# 08_LMS7002M_2_Power.net
KiCad netlist of a schematic drawn in Altium Designer
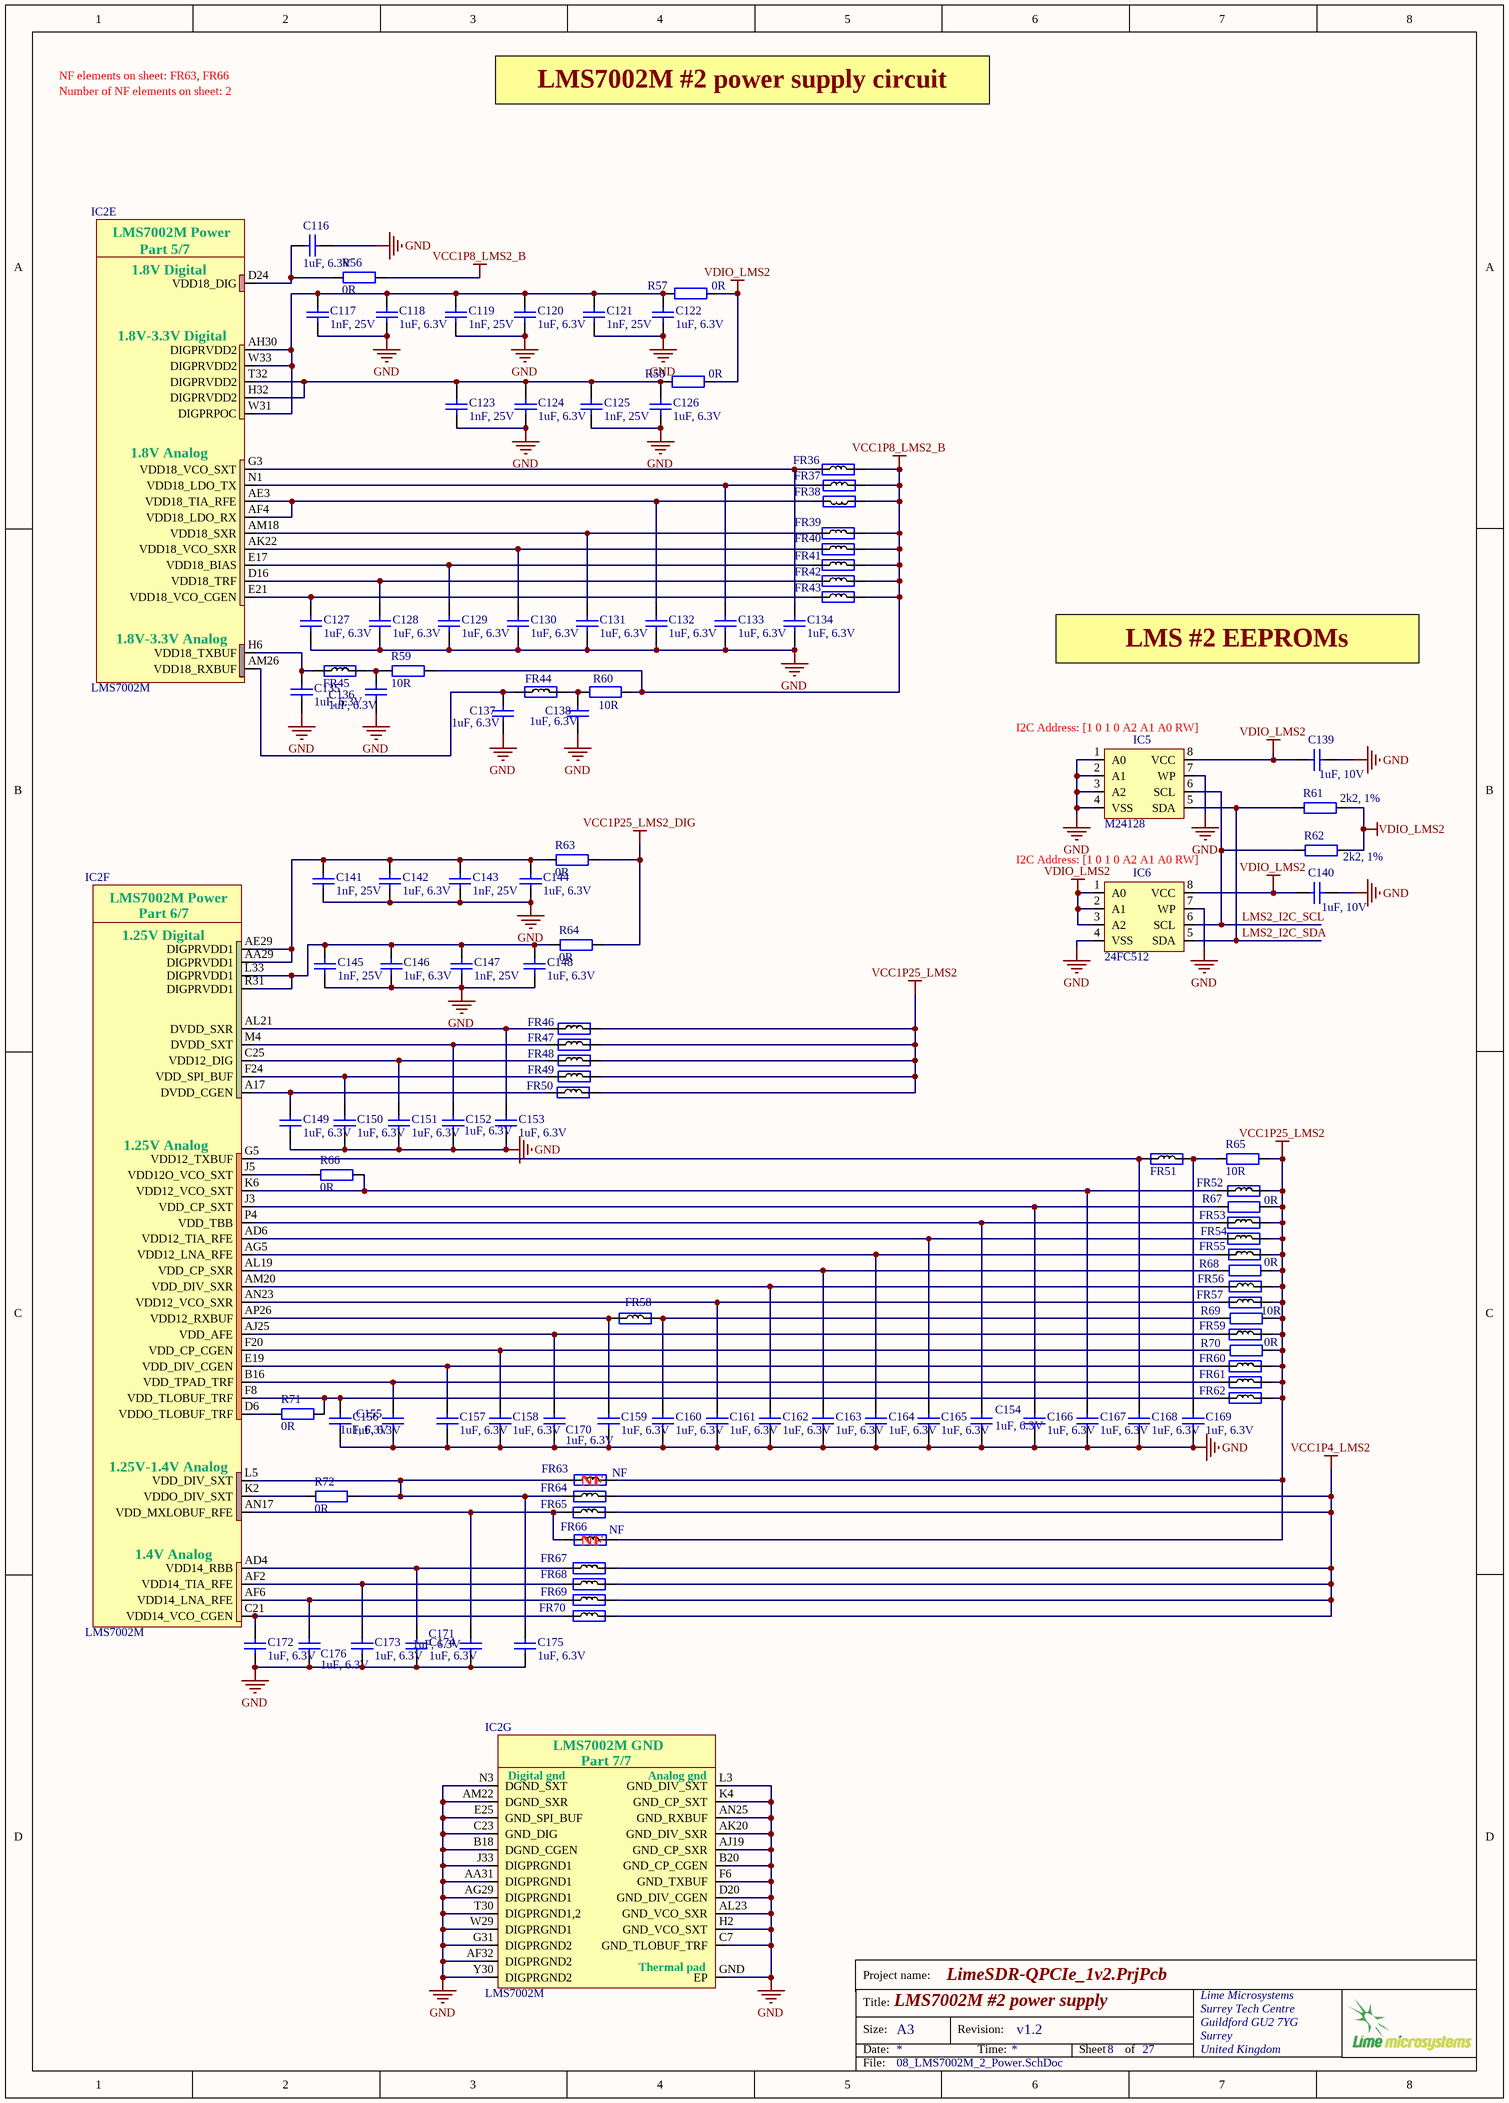
[diagram p0: 08_LMS7002M_2_Power.SchDoc]

(export (version "E")
  (design (tool "Eeschema 10.0.6"))
  (components
    (comp (ref "C116")
      (value "1uF, 6.3V")
      (footprint "CAP0201")
      (fields (field (name "TOLERANCE") "±20%") (field (name "MANUFACTURER") "TDK Corporation"))
      (libsource (lib "LimeMicroAltiumLib_schLib") (part "Cap_0402"))
    )
    (comp (ref "C117")
      (value "1nF, 25V")
      (footprint "CAP0201")
      (fields (field (name "TOLERANCE") "±10%") (field (name "MANUFACTURER") "TDK Corporation"))
      (libsource (lib "LimeMicroAltiumLib_schLib") (part "Cap_0402"))
    )
    (comp (ref "C118")
      (value "1uF, 6.3V")
      (footprint "CAP0201")
      (fields (field (name "TOLERANCE") "±20%") (field (name "MANUFACTURER") "TDK Corporation"))
      (libsource (lib "LimeMicroAltiumLib_schLib") (part "Cap_0402"))
    )
    (comp (ref "C119")
      (value "1nF, 25V")
      (footprint "CAP0201")
      (fields (field (name "TOLERANCE") "±10%") (field (name "MANUFACTURER") "TDK Corporation"))
      (libsource (lib "LimeMicroAltiumLib_schLib") (part "Cap_0402"))
    )
    (comp (ref "C120")
      (value "1uF, 6.3V")
      (footprint "CAP0201")
      (fields (field (name "TOLERANCE") "±20%") (field (name "MANUFACTURER") "TDK Corporation"))
      (libsource (lib "LimeMicroAltiumLib_schLib") (part "Cap_0402"))
    )
    (comp (ref "C121")
      (value "1nF, 25V")
      (footprint "CAP0201")
      (fields (field (name "TOLERANCE") "±10%") (field (name "MANUFACTURER") "TDK Corporation"))
      (libsource (lib "LimeMicroAltiumLib_schLib") (part "Cap_0402"))
    )
    (comp (ref "C122")
      (value "1uF, 6.3V")
      (footprint "CAP0201")
      (fields (field (name "TOLERANCE") "±20%") (field (name "MANUFACTURER") "TDK Corporation"))
      (libsource (lib "LimeMicroAltiumLib_schLib") (part "Cap_0402"))
    )
    (comp (ref "C123")
      (value "1nF, 25V")
      (footprint "CAP0201")
      (fields (field (name "TOLERANCE") "±10%") (field (name "MANUFACTURER") "TDK Corporation"))
      (libsource (lib "LimeMicroAltiumLib_schLib") (part "Cap_0402"))
    )
    (comp (ref "C124")
      (value "1uF, 6.3V")
      (footprint "CAP0201")
      (fields (field (name "TOLERANCE") "±20%") (field (name "MANUFACTURER") "TDK Corporation"))
      (libsource (lib "LimeMicroAltiumLib_schLib") (part "Cap_0402"))
    )
    (comp (ref "C125")
      (value "1nF, 25V")
      (footprint "CAP0201")
      (fields (field (name "TOLERANCE") "±10%") (field (name "MANUFACTURER") "TDK Corporation"))
      (libsource (lib "LimeMicroAltiumLib_schLib") (part "Cap_0402"))
    )
    (comp (ref "C126")
      (value "1uF, 6.3V")
      (footprint "CAP0201")
      (fields (field (name "TOLERANCE") "±20%") (field (name "MANUFACTURER") "TDK Corporation"))
      (libsource (lib "LimeMicroAltiumLib_schLib") (part "Cap_0402"))
    )
    (comp (ref "C127")
      (value "1uF, 6.3V")
      (footprint "CAP0201")
      (fields (field (name "TOLERANCE") "±20%") (field (name "MANUFACTURER") "TDK Corporation"))
      (libsource (lib "LimeMicroAltiumLib_schLib") (part "Cap_0402"))
    )
    (comp (ref "C128")
      (value "1uF, 6.3V")
      (footprint "CAP0201")
      (fields (field (name "TOLERANCE") "±20%") (field (name "MANUFACTURER") "TDK Corporation"))
      (libsource (lib "LimeMicroAltiumLib_schLib") (part "Cap_0402"))
    )
    (comp (ref "C129")
      (value "1uF, 6.3V")
      (footprint "CAP0201")
      (fields (field (name "TOLERANCE") "±20%") (field (name "MANUFACTURER") "TDK Corporation"))
      (libsource (lib "LimeMicroAltiumLib_schLib") (part "Cap_0402"))
    )
    (comp (ref "C130")
      (value "1uF, 6.3V")
      (footprint "CAP0201")
      (fields (field (name "TOLERANCE") "±20%") (field (name "MANUFACTURER") "TDK Corporation"))
      (libsource (lib "LimeMicroAltiumLib_schLib") (part "Cap_0402"))
    )
    (comp (ref "C131")
      (value "1uF, 6.3V")
      (footprint "CAP0201")
      (fields (field (name "TOLERANCE") "±20%") (field (name "MANUFACTURER") "TDK Corporation"))
      (libsource (lib "LimeMicroAltiumLib_schLib") (part "Cap_0402"))
    )
    (comp (ref "C132")
      (value "1uF, 6.3V")
      (footprint "CAP0201")
      (fields (field (name "TOLERANCE") "±20%") (field (name "MANUFACTURER") "TDK Corporation"))
      (libsource (lib "LimeMicroAltiumLib_schLib") (part "Cap_0402"))
    )
    (comp (ref "C133")
      (value "1uF, 6.3V")
      (footprint "CAP0201")
      (fields (field (name "TOLERANCE") "±20%") (field (name "MANUFACTURER") "TDK Corporation"))
      (libsource (lib "LimeMicroAltiumLib_schLib") (part "Cap_0402"))
    )
    (comp (ref "C134")
      (value "1uF, 6.3V")
      (footprint "CAP0201")
      (fields (field (name "TOLERANCE") "±20%") (field (name "MANUFACTURER") "TDK Corporation"))
      (libsource (lib "LimeMicroAltiumLib_schLib") (part "Cap_0402"))
    )
    (comp (ref "C135")
      (value "1uF, 6.3V")
      (footprint "CAP0201")
      (fields (field (name "TOLERANCE") "±20%") (field (name "MANUFACTURER") "TDK Corporation"))
      (libsource (lib "LimeMicroAltiumLib_schLib") (part "Cap_0402"))
    )
    (comp (ref "C136")
      (value "1uF, 6.3V")
      (footprint "CAP0201")
      (fields (field (name "TOLERANCE") "±20%") (field (name "MANUFACTURER") "TDK Corporation"))
      (libsource (lib "LimeMicroAltiumLib_schLib") (part "Cap_0402"))
    )
    (comp (ref "C137")
      (value "1uF, 6.3V")
      (footprint "CAP0201")
      (fields (field (name "TOLERANCE") "±20%") (field (name "MANUFACTURER") "TDK Corporation"))
      (libsource (lib "LimeMicroAltiumLib_schLib") (part "Cap_0402"))
    )
    (comp (ref "C138")
      (value "1uF, 6.3V")
      (footprint "CAP0201")
      (fields (field (name "TOLERANCE") "±20%") (field (name "MANUFACTURER") "TDK Corporation"))
      (libsource (lib "LimeMicroAltiumLib_schLib") (part "Cap_0402"))
    )
    (comp (ref "C139")
      (value "1uF, 10V")
      (footprint "CAP0402")
      (fields (field (name "MANUFACTURER") "TDK"))
      (libsource (lib "LimeMicroAltiumLib_schLib") (part "Cap_0402"))
    )
    (comp (ref "C140")
      (value "1uF, 10V")
      (footprint "CAP0402")
      (fields (field (name "MANUFACTURER") "TDK"))
      (libsource (lib "LimeMicroAltiumLib_schLib") (part "Cap_0402"))
    )
    (comp (ref "C141")
      (value "1nF, 25V")
      (footprint "CAP0201")
      (fields (field (name "TOLERANCE") "±10%") (field (name "MANUFACTURER") "TDK Corporation"))
      (libsource (lib "LimeMicroAltiumLib_schLib") (part "Cap_0402"))
    )
    (comp (ref "C142")
      (value "1uF, 6.3V")
      (footprint "CAP0201")
      (fields (field (name "TOLERANCE") "±20%") (field (name "MANUFACTURER") "TDK Corporation"))
      (libsource (lib "LimeMicroAltiumLib_schLib") (part "Cap_0402"))
    )
    (comp (ref "C143")
      (value "1nF, 25V")
      (footprint "CAP0201")
      (fields (field (name "TOLERANCE") "±10%") (field (name "MANUFACTURER") "TDK Corporation"))
      (libsource (lib "LimeMicroAltiumLib_schLib") (part "Cap_0402"))
    )
    (comp (ref "C144")
      (value "1uF, 6.3V")
      (footprint "CAP0201")
      (fields (field (name "TOLERANCE") "±20%") (field (name "MANUFACTURER") "TDK Corporation"))
      (libsource (lib "LimeMicroAltiumLib_schLib") (part "Cap_0402"))
    )
    (comp (ref "C145")
      (value "1nF, 25V")
      (footprint "CAP0201")
      (fields (field (name "TOLERANCE") "±10%") (field (name "MANUFACTURER") "TDK Corporation"))
      (libsource (lib "LimeMicroAltiumLib_schLib") (part "Cap_0402"))
    )
    (comp (ref "C146")
      (value "1uF, 6.3V")
      (footprint "CAP0201")
      (fields (field (name "TOLERANCE") "±20%") (field (name "MANUFACTURER") "TDK Corporation"))
      (libsource (lib "LimeMicroAltiumLib_schLib") (part "Cap_0402"))
    )
    (comp (ref "C147")
      (value "1nF, 25V")
      (footprint "CAP0201")
      (fields (field (name "TOLERANCE") "±10%") (field (name "MANUFACTURER") "TDK Corporation"))
      (libsource (lib "LimeMicroAltiumLib_schLib") (part "Cap_0402"))
    )
    (comp (ref "C148")
      (value "1uF, 6.3V")
      (footprint "CAP0201")
      (fields (field (name "TOLERANCE") "±20%") (field (name "MANUFACTURER") "TDK Corporation"))
      (libsource (lib "LimeMicroAltiumLib_schLib") (part "Cap_0402"))
    )
    (comp (ref "C149")
      (value "1uF, 6.3V")
      (footprint "CAP0201")
      (fields (field (name "TOLERANCE") "±20%") (field (name "MANUFACTURER") "TDK Corporation"))
      (libsource (lib "LimeMicroAltiumLib_schLib") (part "Cap_0402"))
    )
    (comp (ref "C150")
      (value "1uF, 6.3V")
      (footprint "CAP0201")
      (fields (field (name "TOLERANCE") "±20%") (field (name "MANUFACTURER") "TDK Corporation"))
      (libsource (lib "LimeMicroAltiumLib_schLib") (part "Cap_0402"))
    )
    (comp (ref "C151")
      (value "1uF, 6.3V")
      (footprint "CAP0201")
      (fields (field (name "TOLERANCE") "±20%") (field (name "MANUFACTURER") "TDK Corporation"))
      (libsource (lib "LimeMicroAltiumLib_schLib") (part "Cap_0402"))
    )
    (comp (ref "C152")
      (value "1uF, 6.3V")
      (footprint "CAP0201")
      (fields (field (name "TOLERANCE") "±20%") (field (name "MANUFACTURER") "TDK Corporation"))
      (libsource (lib "LimeMicroAltiumLib_schLib") (part "Cap_0402"))
    )
    (comp (ref "C153")
      (value "1uF, 6.3V")
      (footprint "CAP0201")
      (fields (field (name "TOLERANCE") "±20%") (field (name "MANUFACTURER") "TDK Corporation"))
      (libsource (lib "LimeMicroAltiumLib_schLib") (part "Cap_0402"))
    )
    (comp (ref "C154")
      (value "1uF, 6.3V")
      (footprint "CAP0201")
      (fields (field (name "TOLERANCE") "±20%") (field (name "MANUFACTURER") "TDK Corporation"))
      (libsource (lib "LimeMicroAltiumLib_schLib") (part "Cap_0402"))
    )
    (comp (ref "C155")
      (value "1uF, 6.3V")
      (footprint "CAP0201")
      (fields (field (name "TOLERANCE") "±20%") (field (name "MANUFACTURER") "TDK Corporation"))
      (libsource (lib "LimeMicroAltiumLib_schLib") (part "Cap_0402"))
    )
    (comp (ref "C156")
      (value "1uF, 6.3V")
      (footprint "CAP0201")
      (fields (field (name "TOLERANCE") "±20%") (field (name "MANUFACTURER") "TDK Corporation"))
      (libsource (lib "LimeMicroAltiumLib_schLib") (part "Cap_0402"))
    )
    (comp (ref "C157")
      (value "1uF, 6.3V")
      (footprint "CAP0201")
      (fields (field (name "TOLERANCE") "±20%") (field (name "MANUFACTURER") "TDK Corporation"))
      (libsource (lib "LimeMicroAltiumLib_schLib") (part "Cap_0402"))
    )
    (comp (ref "C158")
      (value "1uF, 6.3V")
      (footprint "CAP0201")
      (fields (field (name "TOLERANCE") "±20%") (field (name "MANUFACTURER") "TDK Corporation"))
      (libsource (lib "LimeMicroAltiumLib_schLib") (part "Cap_0402"))
    )
    (comp (ref "C159")
      (value "1uF, 6.3V")
      (footprint "CAP0201")
      (fields (field (name "TOLERANCE") "±20%") (field (name "MANUFACTURER") "TDK Corporation"))
      (libsource (lib "LimeMicroAltiumLib_schLib") (part "Cap_0402"))
    )
    (comp (ref "C160")
      (value "1uF, 6.3V")
      (footprint "CAP0201")
      (fields (field (name "TOLERANCE") "±20%") (field (name "MANUFACTURER") "TDK Corporation"))
      (libsource (lib "LimeMicroAltiumLib_schLib") (part "Cap_0402"))
    )
    (comp (ref "C161")
      (value "1uF, 6.3V")
      (footprint "CAP0201")
      (fields (field (name "TOLERANCE") "±20%") (field (name "MANUFACTURER") "TDK Corporation"))
      (libsource (lib "LimeMicroAltiumLib_schLib") (part "Cap_0402"))
    )
    (comp (ref "C162")
      (value "1uF, 6.3V")
      (footprint "CAP0201")
      (fields (field (name "TOLERANCE") "±20%") (field (name "MANUFACTURER") "TDK Corporation"))
      (libsource (lib "LimeMicroAltiumLib_schLib") (part "Cap_0402"))
    )
    (comp (ref "C163")
      (value "1uF, 6.3V")
      (footprint "CAP0201")
      (fields (field (name "TOLERANCE") "±20%") (field (name "MANUFACTURER") "TDK Corporation"))
      (libsource (lib "LimeMicroAltiumLib_schLib") (part "Cap_0402"))
    )
    (comp (ref "C164")
      (value "1uF, 6.3V")
      (footprint "CAP0201")
      (fields (field (name "TOLERANCE") "±20%") (field (name "MANUFACTURER") "TDK Corporation"))
      (libsource (lib "LimeMicroAltiumLib_schLib") (part "Cap_0402"))
    )
    (comp (ref "C165")
      (value "1uF, 6.3V")
      (footprint "CAP0201")
      (fields (field (name "TOLERANCE") "±20%") (field (name "MANUFACTURER") "TDK Corporation"))
      (libsource (lib "LimeMicroAltiumLib_schLib") (part "Cap_0402"))
    )
    (comp (ref "C166")
      (value "1uF, 6.3V")
      (footprint "CAP0201")
      (fields (field (name "TOLERANCE") "±20%") (field (name "MANUFACTURER") "TDK Corporation"))
      (libsource (lib "LimeMicroAltiumLib_schLib") (part "Cap_0402"))
    )
    (comp (ref "C167")
      (value "1uF, 6.3V")
      (footprint "CAP0201")
      (fields (field (name "TOLERANCE") "±20%") (field (name "MANUFACTURER") "TDK Corporation"))
      (libsource (lib "LimeMicroAltiumLib_schLib") (part "Cap_0402"))
    )
    (comp (ref "C168")
      (value "1uF, 6.3V")
      (footprint "CAP0201")
      (fields (field (name "TOLERANCE") "±20%") (field (name "MANUFACTURER") "TDK Corporation"))
      (libsource (lib "LimeMicroAltiumLib_schLib") (part "Cap_0402"))
    )
    (comp (ref "C169")
      (value "1uF, 6.3V")
      (footprint "CAP0201")
      (fields (field (name "TOLERANCE") "±20%") (field (name "MANUFACTURER") "TDK Corporation"))
      (libsource (lib "LimeMicroAltiumLib_schLib") (part "Cap_0402"))
    )
    (comp (ref "C170")
      (value "1uF, 6.3V")
      (footprint "CAP0201")
      (fields (field (name "TOLERANCE") "±20%") (field (name "MANUFACTURER") "TDK Corporation"))
      (libsource (lib "LimeMicroAltiumLib_schLib") (part "Cap_0402"))
    )
    (comp (ref "C171")
      (value "1uF, 6.3V")
      (footprint "CAP0201")
      (fields (field (name "TOLERANCE") "±20%") (field (name "MANUFACTURER") "TDK Corporation"))
      (libsource (lib "LimeMicroAltiumLib_schLib") (part "Cap_0402"))
    )
    (comp (ref "C172")
      (value "1uF, 6.3V")
      (footprint "CAP0201")
      (fields (field (name "TOLERANCE") "±20%") (field (name "MANUFACTURER") "TDK Corporation"))
      (libsource (lib "LimeMicroAltiumLib_schLib") (part "Cap_0402"))
    )
    (comp (ref "C173")
      (value "1uF, 6.3V")
      (footprint "CAP0201")
      (fields (field (name "TOLERANCE") "±20%") (field (name "MANUFACTURER") "TDK Corporation"))
      (libsource (lib "LimeMicroAltiumLib_schLib") (part "Cap_0402"))
    )
    (comp (ref "C174")
      (value "1uF, 6.3V")
      (footprint "CAP0201")
      (fields (field (name "TOLERANCE") "±20%") (field (name "MANUFACTURER") "TDK Corporation"))
      (libsource (lib "LimeMicroAltiumLib_schLib") (part "Cap_0402"))
    )
    (comp (ref "C175")
      (value "1uF, 6.3V")
      (footprint "CAP0201")
      (fields (field (name "TOLERANCE") "±20%") (field (name "MANUFACTURER") "TDK Corporation"))
      (libsource (lib "LimeMicroAltiumLib_schLib") (part "Cap_0402"))
    )
    (comp (ref "C176")
      (value "1uF, 6.3V")
      (footprint "CAP0201")
      (fields (field (name "TOLERANCE") "±20%") (field (name "MANUFACTURER") "TDK Corporation"))
      (libsource (lib "LimeMicroAltiumLib_schLib") (part "Cap_0402"))
    )
    (comp (ref "FR36")
      (value "Ferrite")
      (footprint "RES0201")
      (fields (field (name "MANUFACTURER") "Taiyo Yuden"))
      (libsource (lib "LimeMicroAltiumLib_schLib") (part "Ferrite"))
    )
    (comp (ref "FR37")
      (value "Ferrite")
      (footprint "RES0201")
      (fields (field (name "MANUFACTURER") "Taiyo Yuden"))
      (libsource (lib "") (part "Ferrite_1"))
    )
    (comp (ref "FR38")
      (value "Ferrite")
      (footprint "RES0201")
      (fields (field (name "MANUFACTURER") "Taiyo Yuden"))
      (libsource (lib "LimeMicroAltiumLib_schLib") (part "Ferrite"))
    )
    (comp (ref "FR39")
      (value "Ferrite")
      (footprint "RES0201")
      (fields (field (name "MANUFACTURER") "Taiyo Yuden"))
      (libsource (lib "LimeMicroAltiumLib_schLib") (part "Ferrite"))
    )
    (comp (ref "FR40")
      (value "Ferrite")
      (footprint "RES0201")
      (fields (field (name "MANUFACTURER") "Taiyo Yuden"))
      (libsource (lib "LimeMicroAltiumLib_schLib") (part "Ferrite"))
    )
    (comp (ref "FR41")
      (value "Ferrite")
      (footprint "RES0201")
      (fields (field (name "MANUFACTURER") "Taiyo Yuden"))
      (libsource (lib "LimeMicroAltiumLib_schLib") (part "Ferrite"))
    )
    (comp (ref "FR42")
      (value "Ferrite")
      (footprint "RES0201")
      (fields (field (name "MANUFACTURER") "Taiyo Yuden"))
      (libsource (lib "LimeMicroAltiumLib_schLib") (part "Ferrite"))
    )
    (comp (ref "FR43")
      (value "Ferrite")
      (footprint "RES0201")
      (fields (field (name "MANUFACTURER") "Taiyo Yuden"))
      (libsource (lib "LimeMicroAltiumLib_schLib") (part "Ferrite"))
    )
    (comp (ref "FR44")
      (value "Ferrite")
      (footprint "RES0201")
      (fields (field (name "MANUFACTURER") "Taiyo Yuden"))
      (libsource (lib "LimeMicroAltiumLib_schLib") (part "Ferrite"))
    )
    (comp (ref "FR45")
      (value "Ferrite")
      (footprint "RES0201")
      (fields (field (name "MANUFACTURER") "Taiyo Yuden"))
      (libsource (lib "") (part "Ferrite_1"))
    )
    (comp (ref "FR46")
      (value "Ferrite")
      (footprint "RES0201")
      (fields (field (name "MANUFACTURER") "Taiyo Yuden"))
      (libsource (lib "") (part "Ferrite_1"))
    )
    (comp (ref "FR47")
      (value "Ferrite")
      (footprint "RES0201")
      (fields (field (name "MANUFACTURER") "Taiyo Yuden"))
      (libsource (lib "") (part "Ferrite_1"))
    )
    (comp (ref "FR48")
      (value "Ferrite")
      (footprint "RES0201")
      (fields (field (name "MANUFACTURER") "Taiyo Yuden"))
      (libsource (lib "") (part "Ferrite_1"))
    )
    (comp (ref "FR49")
      (value "Ferrite")
      (footprint "RES0201")
      (fields (field (name "MANUFACTURER") "Taiyo Yuden"))
      (libsource (lib "") (part "Ferrite_1"))
    )
    (comp (ref "FR50")
      (value "Ferrite")
      (footprint "RES0201")
      (fields (field (name "MANUFACTURER") "Taiyo Yuden"))
      (libsource (lib "LimeMicroAltiumLib_schLib") (part "Ferrite"))
    )
    (comp (ref "FR51")
      (value "Ferrite")
      (footprint "RES0201")
      (fields (field (name "MANUFACTURER") "Taiyo Yuden"))
      (libsource (lib "") (part "Ferrite_1"))
    )
    (comp (ref "FR52")
      (value "Ferrite")
      (footprint "RES0201")
      (fields (field (name "MANUFACTURER") "Taiyo Yuden"))
      (libsource (lib "") (part "Ferrite_1"))
    )
    (comp (ref "FR53")
      (value "Ferrite")
      (footprint "RES0201")
      (fields (field (name "MANUFACTURER") "Taiyo Yuden"))
      (libsource (lib "") (part "Ferrite_1"))
    )
    (comp (ref "FR54")
      (value "Ferrite")
      (footprint "RES0201")
      (fields (field (name "MANUFACTURER") "Taiyo Yuden"))
      (libsource (lib "") (part "Ferrite_1"))
    )
    (comp (ref "FR55")
      (value "Ferrite")
      (footprint "RES0201")
      (fields (field (name "MANUFACTURER") "Taiyo Yuden"))
      (libsource (lib "") (part "Ferrite_1"))
    )
    (comp (ref "FR56")
      (value "Ferrite")
      (footprint "RES0201")
      (fields (field (name "MANUFACTURER") "Taiyo Yuden"))
      (libsource (lib "LimeMicroAltiumLib_schLib") (part "Ferrite"))
    )
    (comp (ref "FR57")
      (value "Ferrite")
      (footprint "RES0201")
      (fields (field (name "MANUFACTURER") "Taiyo Yuden"))
      (libsource (lib "LimeMicroAltiumLib_schLib") (part "Ferrite"))
    )
    (comp (ref "FR58")
      (value "Ferrite")
      (footprint "RES0201")
      (fields (field (name "MANUFACTURER") "Taiyo Yuden"))
      (libsource (lib "LimeMicroAltiumLib_schLib") (part "Ferrite"))
    )
    (comp (ref "FR59")
      (value "Ferrite")
      (footprint "RES0201")
      (fields (field (name "MANUFACTURER") "Taiyo Yuden"))
      (libsource (lib "LimeMicroAltiumLib_schLib") (part "Ferrite"))
    )
    (comp (ref "FR60")
      (value "Ferrite")
      (footprint "RES0201")
      (fields (field (name "MANUFACTURER") "Taiyo Yuden"))
      (libsource (lib "LimeMicroAltiumLib_schLib") (part "Ferrite"))
    )
    (comp (ref "FR61")
      (value "Ferrite")
      (footprint "RES0201")
      (fields (field (name "MANUFACTURER") "Taiyo Yuden"))
      (libsource (lib "LimeMicroAltiumLib_schLib") (part "Ferrite"))
    )
    (comp (ref "FR62")
      (value "Ferrite")
      (footprint "RES0201")
      (fields (field (name "MANUFACTURER") "Taiyo Yuden"))
      (libsource (lib "LimeMicroAltiumLib_schLib") (part "Ferrite"))
    )
    (comp (ref "FR63")
      (value "Ferrite")
      (footprint "RES0201")
      (fields (field (name "MANUFACTURER") "Taiyo Yuden") (field (name "ASSEMBLY INFO") "NF"))
      (libsource (lib "") (part "Ferrite_1"))
    )
    (comp (ref "FR64")
      (value "Ferrite")
      (footprint "RES0201")
      (fields (field (name "MANUFACTURER") "Taiyo Yuden"))
      (libsource (lib "") (part "Ferrite_1"))
    )
    (comp (ref "FR65")
      (value "Ferrite")
      (footprint "RES0201")
      (fields (field (name "MANUFACTURER") "Taiyo Yuden"))
      (libsource (lib "LimeMicroAltiumLib_schLib") (part "Ferrite"))
    )
    (comp (ref "FR66")
      (value "Ferrite")
      (footprint "RES0201")
      (fields (field (name "MANUFACTURER") "Taiyo Yuden") (field (name "ASSEMBLY INFO") "NF"))
      (libsource (lib "LimeMicroAltiumLib_schLib") (part "Ferrite"))
    )
    (comp (ref "FR67")
      (value "Ferrite")
      (footprint "RES0201")
      (fields (field (name "MANUFACTURER") "Taiyo Yuden"))
      (libsource (lib "LimeMicroAltiumLib_schLib") (part "Ferrite"))
    )
    (comp (ref "FR68")
      (value "Ferrite")
      (footprint "RES0201")
      (fields (field (name "MANUFACTURER") "Taiyo Yuden"))
      (libsource (lib "LimeMicroAltiumLib_schLib") (part "Ferrite"))
    )
    (comp (ref "FR69")
      (value "Ferrite")
      (footprint "RES0201")
      (fields (field (name "MANUFACTURER") "Taiyo Yuden"))
      (libsource (lib "LimeMicroAltiumLib_schLib") (part "Ferrite"))
    )
    (comp (ref "FR70")
      (value "Ferrite")
      (footprint "RES0201")
      (fields (field (name "MANUFACTURER") "Taiyo Yuden"))
      (libsource (lib "LimeMicroAltiumLib_schLib") (part "Ferrite"))
    )
    (comp (ref "IC2")
      (value "LMS7002M")
      (footprint "LMS7002M_v4")
      (description "Schematic symbol revision 3. Default footprint - 0.31mm pad")
      (fields (field (name "MANUFACTURER") "Lime Microsystems"))
      (libsource (lib "LimeMicroAltiumLib_schLib") (part "LMS7002Mr3"))
    )
    (comp (ref "IC5")
      (value "M24128")
      (footprint "24FC512")
      (fields (field (name "MANUFACTURER") "STMicroelectronics"))
      (libsource (lib "LimeMicroAltiumLib_schLib") (part "24FC64F"))
    )
    (comp (ref "IC6")
      (value "24FC512")
      (footprint "24FC512")
      (fields (field (name "MANUFACTURER") "Microchip Technology"))
      (libsource (lib "LimeMicroAltiumLib_schLib") (part "24FC512"))
    )
    (comp (ref "R56")
      (value "0R")
      (footprint "RES0201")
      (fields (field (name "MANUFACTURER") "Rohm Semiconductor") (field (name "TOLERANCE") "Jumper"))
      (libsource (lib "LimeMicroAltiumLib_schLib") (part "Res_0402"))
    )
    (comp (ref "R57")
      (value "0R")
      (footprint "RES0402")
      (fields (field (name "MANUFACTURER") "Yageo") (field (name "TOLERANCE") "Jumper"))
      (libsource (lib "LimeMicroAltiumLib_schLib") (part "Res_0402"))
    )
    (comp (ref "R58")
      (value "0R")
      (footprint "RES0402")
      (fields (field (name "MANUFACTURER") "Yageo") (field (name "TOLERANCE") "Jumper"))
      (libsource (lib "LimeMicroAltiumLib_schLib") (part "Res_0402"))
    )
    (comp (ref "R59")
      (value "10R")
      (footprint "RES0201")
      (fields
        (field (name "MANUFACTURER") "Panasonic Electronic Components")
        (field (name "TOLERANCE") "±1%")
      )
      (libsource (lib "LimeMicroAltiumLib_schLib") (part "Res_0402"))
    )
    (comp (ref "R60")
      (value "10R")
      (footprint "RES0201")
      (fields
        (field (name "MANUFACTURER") "Panasonic Electronic Components")
        (field (name "TOLERANCE") "±1%")
      )
      (libsource (lib "LimeMicroAltiumLib_schLib") (part "Res_0402"))
    )
    (comp (ref "R61")
      (value "2k2, 1%")
      (footprint "RES0402")
      (fields (field (name "MANUFACTURER") "Stackpole Electronics Inc") (field (name "TOLERANCE") "±1%"))
      (libsource (lib "LimeMicroAltiumLib_schLib") (part "Res_0402"))
    )
    (comp (ref "R62")
      (value "2k2, 1%")
      (footprint "RES0402")
      (fields (field (name "MANUFACTURER") "Stackpole Electronics Inc") (field (name "TOLERANCE") "±1%"))
      (libsource (lib "LimeMicroAltiumLib_schLib") (part "Res_0402"))
    )
    (comp (ref "R63")
      (value "0R")
      (footprint "RES0402")
      (fields (field (name "MANUFACTURER") "Yageo") (field (name "TOLERANCE") "Jumper"))
      (libsource (lib "LimeMicroAltiumLib_schLib") (part "Res_0402"))
    )
    (comp (ref "R64")
      (value "0R")
      (footprint "RES0402")
      (fields (field (name "MANUFACTURER") "Yageo") (field (name "TOLERANCE") "Jumper"))
      (libsource (lib "LimeMicroAltiumLib_schLib") (part "Res_0402"))
    )
    (comp (ref "R65")
      (value "10R")
      (footprint "RES0201")
      (fields
        (field (name "MANUFACTURER") "Panasonic Electronic Components")
        (field (name "TOLERANCE") "±1%")
      )
      (libsource (lib "LimeMicroAltiumLib_schLib") (part "Res_0402"))
    )
    (comp (ref "R66")
      (value "0R")
      (footprint "RES0201")
      (fields (field (name "MANUFACTURER") "Rohm Semiconductor") (field (name "TOLERANCE") "Jumper"))
      (libsource (lib "LimeMicroAltiumLib_schLib") (part "Res_0402"))
    )
    (comp (ref "R67")
      (value "0R")
      (footprint "RES0201")
      (fields (field (name "MANUFACTURER") "Rohm Semiconductor") (field (name "TOLERANCE") "Jumper"))
      (libsource (lib "LimeMicroAltiumLib_schLib") (part "Res_0402"))
    )
    (comp (ref "R68")
      (value "0R")
      (footprint "RES0201")
      (fields (field (name "MANUFACTURER") "Rohm Semiconductor") (field (name "TOLERANCE") "Jumper"))
      (libsource (lib "LimeMicroAltiumLib_schLib") (part "Res_0402"))
    )
    (comp (ref "R69")
      (value "10R")
      (footprint "RES0201")
      (fields
        (field (name "MANUFACTURER") "Panasonic Electronic Components")
        (field (name "TOLERANCE") "±1%")
      )
      (libsource (lib "LimeMicroAltiumLib_schLib") (part "Res_0402"))
    )
    (comp (ref "R70")
      (value "0R")
      (footprint "RES0201")
      (fields (field (name "MANUFACTURER") "Rohm Semiconductor") (field (name "TOLERANCE") "Jumper"))
      (libsource (lib "LimeMicroAltiumLib_schLib") (part "Res_0402"))
    )
    (comp (ref "R71")
      (value "0R")
      (footprint "RES0201")
      (fields (field (name "MANUFACTURER") "Rohm Semiconductor") (field (name "TOLERANCE") "Jumper"))
      (libsource (lib "LimeMicroAltiumLib_schLib") (part "Res_0402"))
    )
    (comp (ref "R72")
      (value "0R")
      (footprint "RES0201")
      (fields (field (name "MANUFACTURER") "Rohm Semiconductor") (field (name "TOLERANCE") "Jumper"))
      (libsource (lib "LimeMicroAltiumLib_schLib") (part "Res_0402"))
    )
  )
  (nets
    (net (code "1") (name "/LMS2_I2C_SCL") (class "Default")
      (node (ref "IC5") (pin "6") (pinfunction "SCL_6") (pintype "passive"))
      (node (ref "IC6") (pin "6") (pinfunction "SCL_6") (pintype "passive"))
      (node (ref "R62") (pin "2") (pinfunction "2_2") (pintype "passive"))
    )
    (net (code "2") (name "/LMS2_I2C_SDA") (class "Default")
      (node (ref "IC5") (pin "5") (pinfunction "SDA_5") (pintype "passive"))
      (node (ref "IC6") (pin "5") (pinfunction "SDA_5") (pintype "passive"))
      (node (ref "R61") (pin "2") (pinfunction "2_2") (pintype "passive"))
    )
    (net (code "3") (name "GND") (class "Default")
      (node (ref "C116") (pin "2") (pinfunction "2_2") (pintype "passive"))
      (node (ref "C117") (pin "2") (pinfunction "2_2") (pintype "passive"))
      (node (ref "C118") (pin "2") (pinfunction "2_2") (pintype "passive"))
      (node (ref "C119") (pin "2") (pinfunction "2_2") (pintype "passive"))
      (node (ref "C120") (pin "2") (pinfunction "2_2") (pintype "passive"))
      (node (ref "C121") (pin "2") (pinfunction "2_2") (pintype "passive"))
      (node (ref "C122") (pin "2") (pinfunction "2_2") (pintype "passive"))
      (node (ref "C123") (pin "2") (pinfunction "2_2") (pintype "passive"))
      (node (ref "C124") (pin "2") (pinfunction "2_2") (pintype "passive"))
      (node (ref "C125") (pin "2") (pinfunction "2_2") (pintype "passive"))
      (node (ref "C126") (pin "2") (pinfunction "2_2") (pintype "passive"))
      (node (ref "C127") (pin "2") (pinfunction "2_2") (pintype "passive"))
      (node (ref "C128") (pin "2") (pinfunction "2_2") (pintype "passive"))
      (node (ref "C129") (pin "2") (pinfunction "2_2") (pintype "passive"))
      (node (ref "C130") (pin "2") (pinfunction "2_2") (pintype "passive"))
      (node (ref "C131") (pin "2") (pinfunction "2_2") (pintype "passive"))
      (node (ref "C132") (pin "2") (pinfunction "2_2") (pintype "passive"))
      (node (ref "C133") (pin "2") (pinfunction "2_2") (pintype "passive"))
      (node (ref "C134") (pin "2") (pinfunction "2_2") (pintype "passive"))
      (node (ref "C135") (pin "2") (pinfunction "2_2") (pintype "passive"))
      (node (ref "C136") (pin "2") (pinfunction "2_2") (pintype "passive"))
      (node (ref "C137") (pin "2") (pinfunction "2_2") (pintype "passive"))
      (node (ref "C138") (pin "2") (pinfunction "2_2") (pintype "passive"))
      (node (ref "C139") (pin "1") (pinfunction "1_1") (pintype "passive"))
      (node (ref "C140") (pin "1") (pinfunction "1_1") (pintype "passive"))
      (node (ref "C141") (pin "2") (pinfunction "2_2") (pintype "passive"))
      (node (ref "C142") (pin "2") (pinfunction "2_2") (pintype "passive"))
      (node (ref "C143") (pin "2") (pinfunction "2_2") (pintype "passive"))
      (node (ref "C144") (pin "2") (pinfunction "2_2") (pintype "passive"))
      (node (ref "C145") (pin "2") (pinfunction "2_2") (pintype "passive"))
      (node (ref "C146") (pin "2") (pinfunction "2_2") (pintype "passive"))
      (node (ref "C147") (pin "2") (pinfunction "2_2") (pintype "passive"))
      (node (ref "C148") (pin "2") (pinfunction "2_2") (pintype "passive"))
      (node (ref "C149") (pin "2") (pinfunction "2_2") (pintype "passive"))
      (node (ref "C150") (pin "2") (pinfunction "2_2") (pintype "passive"))
      (node (ref "C151") (pin "2") (pinfunction "2_2") (pintype "passive"))
      (node (ref "C152") (pin "2") (pinfunction "2_2") (pintype "passive"))
      (node (ref "C153") (pin "2") (pinfunction "2_2") (pintype "passive"))
      (node (ref "C154") (pin "2") (pinfunction "2_2") (pintype "passive"))
      (node (ref "C155") (pin "2") (pinfunction "2_2") (pintype "passive"))
      (node (ref "C156") (pin "2") (pinfunction "2_2") (pintype "passive"))
      (node (ref "C157") (pin "2") (pinfunction "2_2") (pintype "passive"))
      (node (ref "C158") (pin "2") (pinfunction "2_2") (pintype "passive"))
      (node (ref "C159") (pin "2") (pinfunction "2_2") (pintype "passive"))
      (node (ref "C160") (pin "2") (pinfunction "2_2") (pintype "passive"))
      (node (ref "C161") (pin "2") (pinfunction "2_2") (pintype "passive"))
      (node (ref "C162") (pin "2") (pinfunction "2_2") (pintype "passive"))
      (node (ref "C163") (pin "2") (pinfunction "2_2") (pintype "passive"))
      (node (ref "C164") (pin "2") (pinfunction "2_2") (pintype "passive"))
      (node (ref "C165") (pin "2") (pinfunction "2_2") (pintype "passive"))
      (node (ref "C166") (pin "2") (pinfunction "2_2") (pintype "passive"))
      (node (ref "C167") (pin "1") (pinfunction "1_1") (pintype "passive"))
      (node (ref "C168") (pin "2") (pinfunction "2_2") (pintype "passive"))
      (node (ref "C169") (pin "2") (pinfunction "2_2") (pintype "passive"))
      (node (ref "C170") (pin "2") (pinfunction "2_2") (pintype "passive"))
      (node (ref "C171") (pin "2") (pinfunction "2_2") (pintype "passive"))
      (node (ref "C172") (pin "2") (pinfunction "2_2") (pintype "passive"))
      (node (ref "C173") (pin "2") (pinfunction "2_2") (pintype "passive"))
      (node (ref "C174") (pin "2") (pinfunction "2_2") (pintype "passive"))
      (node (ref "C175") (pin "2") (pinfunction "2_2") (pintype "passive"))
      (node (ref "C176") (pin "2") (pinfunction "2_2") (pintype "passive"))
      (node (ref "IC2") (pin "AA31") (pinfunction "DIGPRGND1_AA31") (pintype "passive"))
      (node (ref "IC2") (pin "AF32") (pinfunction "DIGPRGND2_AF32") (pintype "passive"))
      (node (ref "IC2") (pin "AG29") (pinfunction "DIGPRGND1_AG29") (pintype "passive"))
      (node (ref "IC2") (pin "AJ19") (pinfunction "GND_CP_SXR_AJ19") (pintype "passive"))
      (node (ref "IC2") (pin "AK20") (pinfunction "GND_DIV_SXR_AK20") (pintype "passive"))
      (node (ref "IC2") (pin "AL23") (pinfunction "GND_VCO_SXR_AL23") (pintype "passive"))
      (node (ref "IC2") (pin "AM22") (pinfunction "DGND_SXR_AM22") (pintype "passive"))
      (node (ref "IC2") (pin "AN25") (pinfunction "GND_RXBUF_AN25") (pintype "passive"))
      (node (ref "IC2") (pin "B18") (pinfunction "DGND_CGEN_B18") (pintype "passive"))
      (node (ref "IC2") (pin "B20") (pinfunction "GND_CP_CGEN_B20") (pintype "passive"))
      (node (ref "IC2") (pin "C23") (pinfunction "GND_DIG_C23") (pintype "passive"))
      (node (ref "IC2") (pin "C7") (pinfunction "GND_TLOBUF_TRF_C7") (pintype "passive"))
      (node (ref "IC2") (pin "D20") (pinfunction "GND_DIV_CGEN_D20") (pintype "passive"))
      (node (ref "IC2") (pin "E25") (pinfunction "GND_SPI_BUF_E25") (pintype "passive"))
      (node (ref "IC2") (pin "F6") (pinfunction "GND_TXBUF_F6") (pintype "passive"))
      (node (ref "IC2") (pin "G31") (pinfunction "DIGPRGND2_G31") (pintype "passive"))
      (node (ref "IC2") (pin "GND") (pinfunction "EP_GND") (pintype "passive"))
      (node (ref "IC2") (pin "H2") (pinfunction "GND_VCO_SXT_H2") (pintype "passive"))
      (node (ref "IC2") (pin "J33") (pinfunction "DIGPRGND1_J33") (pintype "passive"))
      (node (ref "IC2") (pin "K4") (pinfunction "GND_CP_SXT_K4") (pintype "passive"))
      (node (ref "IC2") (pin "L3") (pinfunction "GND_DIV_SXT_L3") (pintype "passive"))
      (node (ref "IC2") (pin "N3") (pinfunction "DGND_SXT_N3") (pintype "passive"))
      (node (ref "IC2") (pin "T30") (pinfunction "DIGPRGND1,2_T30") (pintype "passive"))
      (node (ref "IC2") (pin "W29") (pinfunction "DIGPRGND1_W29") (pintype "passive"))
      (node (ref "IC2") (pin "Y30") (pinfunction "DIGPRGND2_Y30") (pintype "passive"))
      (node (ref "IC5") (pin "1") (pinfunction "A0_1") (pintype "passive"))
      (node (ref "IC5") (pin "2") (pinfunction "A1_2") (pintype "passive"))
      (node (ref "IC5") (pin "3") (pinfunction "A2_3") (pintype "passive"))
      (node (ref "IC5") (pin "4") (pinfunction "VSS_4") (pintype "passive"))
      (node (ref "IC5") (pin "7") (pinfunction "WP_7") (pintype "passive"))
      (node (ref "IC6") (pin "4") (pinfunction "VSS_4") (pintype "passive"))
      (node (ref "IC6") (pin "7") (pinfunction "WP_7") (pintype "passive"))
    )
    (net (code "4") (name "Net-(C123-Pad1)") (class "Default")
      (node (ref "C123") (pin "1") (pinfunction "1_1") (pintype "passive"))
      (node (ref "C124") (pin "1") (pinfunction "1_1") (pintype "passive"))
      (node (ref "C125") (pin "1") (pinfunction "1_1") (pintype "passive"))
      (node (ref "C126") (pin "1") (pinfunction "1_1") (pintype "passive"))
      (node (ref "IC2") (pin "H32") (pinfunction "DIGPRVDD2_H32") (pintype "power_in"))
      (node (ref "IC2") (pin "T32") (pinfunction "DIGPRVDD2_T32") (pintype "power_in"))
      (node (ref "R58") (pin "2") (pinfunction "2_2") (pintype "passive"))
    )
    (net (code "5") (name "Net-(C136-Pad1)") (class "Default")
      (node (ref "C136") (pin "1") (pinfunction "1_1") (pintype "passive"))
      (node (ref "FR45") (pin "1") (pinfunction "1_1") (pintype "passive"))
      (node (ref "R59") (pin "1") (pinfunction "1_1") (pintype "passive"))
    )
    (net (code "6") (name "Net-(C138-Pad1)") (class "Default")
      (node (ref "C138") (pin "1") (pinfunction "1_1") (pintype "passive"))
      (node (ref "FR44") (pin "2") (pinfunction "2_2") (pintype "passive"))
      (node (ref "R60") (pin "2") (pinfunction "2_2") (pintype "passive"))
    )
    (net (code "7") (name "Net-(C141-Pad1)") (class "Default")
      (node (ref "C141") (pin "1") (pinfunction "1_1") (pintype "passive"))
      (node (ref "C142") (pin "1") (pinfunction "1_1") (pintype "passive"))
      (node (ref "C143") (pin "1") (pinfunction "1_1") (pintype "passive"))
      (node (ref "C144") (pin "1") (pinfunction "1_1") (pintype "passive"))
      (node (ref "IC2") (pin "AA29") (pinfunction "DIGPRVDD1_AA29") (pintype "power_in"))
      (node (ref "IC2") (pin "AE29") (pinfunction "DIGPRVDD1_AE29") (pintype "power_in"))
      (node (ref "R63") (pin "1") (pinfunction "1_1") (pintype "passive"))
    )
    (net (code "8") (name "Net-(C145-Pad1)") (class "Default")
      (node (ref "C145") (pin "1") (pinfunction "1_1") (pintype "passive"))
      (node (ref "C146") (pin "1") (pinfunction "1_1") (pintype "passive"))
      (node (ref "C147") (pin "1") (pinfunction "1_1") (pintype "passive"))
      (node (ref "C148") (pin "1") (pinfunction "1_1") (pintype "passive"))
      (node (ref "IC2") (pin "L33") (pinfunction "DIGPRVDD1_L33") (pintype "power_in"))
      (node (ref "IC2") (pin "R31") (pinfunction "DIGPRVDD1_R31") (pintype "power_in"))
      (node (ref "R64") (pin "1") (pinfunction "1_1") (pintype "passive"))
    )
    (net (code "9") (name "Net-(C160-Pad1)") (class "Default")
      (node (ref "C160") (pin "1") (pinfunction "1_1") (pintype "passive"))
      (node (ref "FR58") (pin "2") (pinfunction "2_2") (pintype "passive"))
      (node (ref "R69") (pin "2") (pinfunction "2_2") (pintype "passive"))
    )
    (net (code "10") (name "Net-(C169-Pad1)") (class "Default")
      (node (ref "C169") (pin "1") (pinfunction "1_1") (pintype "passive"))
      (node (ref "FR51") (pin "1") (pinfunction "1_1") (pintype "passive"))
      (node (ref "R65") (pin "1") (pinfunction "1_1") (pintype "passive"))
    )
    (net (code "11") (name "Net-(IC2E-DIGPRPOC)") (class "Default")
      (node (ref "C117") (pin "1") (pinfunction "1_1") (pintype "passive"))
      (node (ref "C118") (pin "1") (pinfunction "1_1") (pintype "passive"))
      (node (ref "C119") (pin "1") (pinfunction "1_1") (pintype "passive"))
      (node (ref "C120") (pin "1") (pinfunction "1_1") (pintype "passive"))
      (node (ref "C121") (pin "1") (pinfunction "1_1") (pintype "passive"))
      (node (ref "C122") (pin "1") (pinfunction "1_1") (pintype "passive"))
      (node (ref "IC2") (pin "AH30") (pinfunction "DIGPRVDD2_AH30") (pintype "power_in"))
      (node (ref "IC2") (pin "W31") (pinfunction "DIGPRPOC_W31") (pintype "power_in"))
      (node (ref "IC2") (pin "W33") (pinfunction "DIGPRVDD2_W33") (pintype "power_in"))
      (node (ref "R57") (pin "2") (pinfunction "2_2") (pintype "passive"))
    )
    (net (code "12") (name "Net-(IC2E-VDD18_BIAS)") (class "Default")
      (node (ref "C129") (pin "1") (pinfunction "1_1") (pintype "passive"))
      (node (ref "FR41") (pin "1") (pinfunction "1_1") (pintype "passive"))
      (node (ref "IC2") (pin "E17") (pinfunction "VDD18_BIAS_E17") (pintype "power_in"))
    )
    (net (code "13") (name "Net-(IC2E-VDD18_DIG)") (class "Default")
      (node (ref "C116") (pin "1") (pinfunction "1_1") (pintype "passive"))
      (node (ref "IC2") (pin "D24") (pinfunction "VDD18_DIG_D24") (pintype "power_in"))
      (node (ref "R56") (pin "1") (pinfunction "1_1") (pintype "passive"))
    )
    (net (code "14") (name "Net-(IC2E-VDD18_LDO_RX)") (class "Default")
      (node (ref "C132") (pin "1") (pinfunction "1_1") (pintype "passive"))
      (node (ref "FR38") (pin "2") (pinfunction "2_2") (pintype "passive"))
      (node (ref "IC2") (pin "AE3") (pinfunction "VDD18_TIA_RFE_AE3") (pintype "power_in"))
      (node (ref "IC2") (pin "AF4") (pinfunction "VDD18_LDO_RX_AF4") (pintype "power_in"))
    )
    (net (code "15") (name "Net-(IC2E-VDD18_LDO_TX)") (class "Default")
      (node (ref "C133") (pin "1") (pinfunction "1_1") (pintype "passive"))
      (node (ref "FR37") (pin "2") (pinfunction "2_2") (pintype "passive"))
      (node (ref "IC2") (pin "N1") (pinfunction "VDD18_LDO_TX_N1") (pintype "power_in"))
    )
    (net (code "16") (name "Net-(IC2E-VDD18_RXBUF)") (class "Default")
      (node (ref "C137") (pin "1") (pinfunction "1_1") (pintype "passive"))
      (node (ref "FR44") (pin "1") (pinfunction "1_1") (pintype "passive"))
      (node (ref "IC2") (pin "AM26") (pinfunction "VDD18_RXBUF_AM26") (pintype "power_in"))
    )
    (net (code "17") (name "Net-(IC2E-VDD18_SXR)") (class "Default")
      (node (ref "C131") (pin "1") (pinfunction "1_1") (pintype "passive"))
      (node (ref "FR39") (pin "1") (pinfunction "1_1") (pintype "passive"))
      (node (ref "IC2") (pin "AM18") (pinfunction "VDD18_SXR_AM18") (pintype "power_in"))
    )
    (net (code "18") (name "Net-(IC2E-VDD18_TRF)") (class "Default")
      (node (ref "C128") (pin "1") (pinfunction "1_1") (pintype "passive"))
      (node (ref "FR42") (pin "1") (pinfunction "1_1") (pintype "passive"))
      (node (ref "IC2") (pin "D16") (pinfunction "VDD18_TRF_D16") (pintype "power_in"))
    )
    (net (code "19") (name "Net-(IC2E-VDD18_TXBUF)") (class "Default")
      (node (ref "C135") (pin "1") (pinfunction "1_1") (pintype "passive"))
      (node (ref "FR45") (pin "2") (pinfunction "2_2") (pintype "passive"))
      (node (ref "IC2") (pin "H6") (pinfunction "VDD18_TXBUF_H6") (pintype "power_in"))
    )
    (net (code "20") (name "Net-(IC2E-VDD18_VCO_CGEN)") (class "Default")
      (node (ref "C127") (pin "1") (pinfunction "1_1") (pintype "passive"))
      (node (ref "FR43") (pin "1") (pinfunction "1_1") (pintype "passive"))
      (node (ref "IC2") (pin "E21") (pinfunction "VDD18_VCO_CGEN_E21") (pintype "power_in"))
    )
    (net (code "21") (name "Net-(IC2E-VDD18_VCO_SXR)") (class "Default")
      (node (ref "C130") (pin "1") (pinfunction "1_1") (pintype "passive"))
      (node (ref "FR40") (pin "1") (pinfunction "1_1") (pintype "passive"))
      (node (ref "IC2") (pin "AK22") (pinfunction "VDD18_VCO_SXR_AK22") (pintype "power_in"))
    )
    (net (code "22") (name "Net-(IC2E-VDD18_VCO_SXT)") (class "Default")
      (node (ref "C134") (pin "1") (pinfunction "1_1") (pintype "passive"))
      (node (ref "FR36") (pin "1") (pinfunction "1_1") (pintype "passive"))
      (node (ref "IC2") (pin "G3") (pinfunction "VDD18_VCO_SXT_G3") (pintype "power_in"))
    )
    (net (code "23") (name "Net-(IC2F-DVDD_CGEN)") (class "Default")
      (node (ref "C149") (pin "1") (pinfunction "1_1") (pintype "passive"))
      (node (ref "FR50") (pin "1") (pinfunction "1_1") (pintype "passive"))
      (node (ref "IC2") (pin "A17") (pinfunction "DVDD_CGEN_A17") (pintype "power_in"))
    )
    (net (code "24") (name "Net-(IC2F-DVDD_SXR)") (class "Default")
      (node (ref "C153") (pin "1") (pinfunction "1_1") (pintype "passive"))
      (node (ref "FR46") (pin "2") (pinfunction "2_2") (pintype "passive"))
      (node (ref "IC2") (pin "AL21") (pinfunction "DVDD_SXR_AL21") (pintype "power_in"))
    )
    (net (code "25") (name "Net-(IC2F-DVDD_SXT)") (class "Default")
      (node (ref "C152") (pin "1") (pinfunction "1_1") (pintype "passive"))
      (node (ref "FR47") (pin "2") (pinfunction "2_2") (pintype "passive"))
      (node (ref "IC2") (pin "M4") (pinfunction "DVDD_SXT_M4") (pintype "power_in"))
    )
    (net (code "26") (name "Net-(IC2F-VDD12O_VCO_SXT)") (class "Default")
      (node (ref "IC2") (pin "J5") (pinfunction "VDD12O_VCO_SXT_J5") (pintype "power_in"))
      (node (ref "R66") (pin "1") (pinfunction "1_1") (pintype "passive"))
    )
    (net (code "27") (name "Net-(IC2F-VDD12_DIG)") (class "Default")
      (node (ref "C151") (pin "1") (pinfunction "1_1") (pintype "passive"))
      (node (ref "FR48") (pin "2") (pinfunction "2_2") (pintype "passive"))
      (node (ref "IC2") (pin "C25") (pinfunction "VDD12_DIG_C25") (pintype "power_in"))
    )
    (net (code "28") (name "Net-(IC2F-VDD12_LNA_RFE)") (class "Default")
      (node (ref "C164") (pin "1") (pinfunction "1_1") (pintype "passive"))
      (node (ref "FR55") (pin "2") (pinfunction "2_2") (pintype "passive"))
      (node (ref "IC2") (pin "AG5") (pinfunction "VDD12_LNA_RFE_AG5") (pintype "power_in"))
    )
    (net (code "29") (name "Net-(IC2F-VDD12_RXBUF)") (class "Default")
      (node (ref "C159") (pin "1") (pinfunction "1_1") (pintype "passive"))
      (node (ref "FR58") (pin "1") (pinfunction "1_1") (pintype "passive"))
      (node (ref "IC2") (pin "AP26") (pinfunction "VDD12_RXBUF_AP26") (pintype "power_in"))
    )
    (net (code "30") (name "Net-(IC2F-VDD12_TIA_RFE)") (class "Default")
      (node (ref "C165") (pin "1") (pinfunction "1_1") (pintype "passive"))
      (node (ref "FR54") (pin "2") (pinfunction "2_2") (pintype "passive"))
      (node (ref "IC2") (pin "AD6") (pinfunction "VDD12_TIA_RFE_AD6") (pintype "power_in"))
    )
    (net (code "31") (name "Net-(IC2F-VDD12_TXBUF)") (class "Default")
      (node (ref "C168") (pin "1") (pinfunction "1_1") (pintype "passive"))
      (node (ref "FR51") (pin "2") (pinfunction "2_2") (pintype "passive"))
      (node (ref "IC2") (pin "G5") (pinfunction "VDD12_TXBUF_G5") (pintype "power_in"))
    )
    (net (code "32") (name "Net-(IC2F-VDD12_VCO_SXR)") (class "Default")
      (node (ref "C161") (pin "1") (pinfunction "1_1") (pintype "passive"))
      (node (ref "FR57") (pin "1") (pinfunction "1_1") (pintype "passive"))
      (node (ref "IC2") (pin "AN23") (pinfunction "VDD12_VCO_SXR_AN23") (pintype "power_in"))
    )
    (net (code "33") (name "Net-(IC2F-VDD12_VCO_SXT)") (class "Default")
      (node (ref "C167") (pin "2") (pinfunction "2_2") (pintype "passive"))
      (node (ref "FR52") (pin "2") (pinfunction "2_2") (pintype "passive"))
      (node (ref "IC2") (pin "K6") (pinfunction "VDD12_VCO_SXT_K6") (pintype "power_in"))
      (node (ref "R66") (pin "2") (pinfunction "2_2") (pintype "passive"))
    )
    (net (code "34") (name "Net-(IC2F-VDD14_LNA_RFE)") (class "Default")
      (node (ref "C176") (pin "1") (pinfunction "1_1") (pintype "passive"))
      (node (ref "FR69") (pin "1") (pinfunction "1_1") (pintype "passive"))
      (node (ref "IC2") (pin "AF6") (pinfunction "VDD14_LNA_RFE_AF6") (pintype "power_in"))
    )
    (net (code "35") (name "Net-(IC2F-VDD14_RBB)") (class "Default")
      (node (ref "C174") (pin "1") (pinfunction "1_1") (pintype "passive"))
      (node (ref "FR67") (pin "1") (pinfunction "1_1") (pintype "passive"))
      (node (ref "IC2") (pin "AD4") (pinfunction "VDD14_RBB_AD4") (pintype "power_in"))
    )
    (net (code "36") (name "Net-(IC2F-VDD14_TIA_RFE)") (class "Default")
      (node (ref "C173") (pin "1") (pinfunction "1_1") (pintype "passive"))
      (node (ref "FR68") (pin "1") (pinfunction "1_1") (pintype "passive"))
      (node (ref "IC2") (pin "AF2") (pinfunction "VDD14_TIA_RFE_AF2") (pintype "power_in"))
    )
    (net (code "37") (name "Net-(IC2F-VDD14_VCO_CGEN)") (class "Default")
      (node (ref "C172") (pin "1") (pinfunction "1_1") (pintype "passive"))
      (node (ref "FR70") (pin "1") (pinfunction "1_1") (pintype "passive"))
      (node (ref "IC2") (pin "C21") (pinfunction "VDD14_VCO_CGEN_C21") (pintype "power_in"))
    )
    (net (code "38") (name "Net-(IC2F-VDDO_DIV_SXT)") (class "Default")
      (node (ref "IC2") (pin "K2") (pinfunction "VDDO_DIV_SXT_K2") (pintype "power_in"))
      (node (ref "R72") (pin "1") (pinfunction "1_1") (pintype "passive"))
    )
    (net (code "39") (name "Net-(IC2F-VDDO_TLOBUF_TRF)") (class "Default")
      (node (ref "IC2") (pin "D6") (pinfunction "VDDO_TLOBUF_TRF_D6") (pintype "power_in"))
      (node (ref "R71") (pin "2") (pinfunction "2_2") (pintype "passive"))
    )
    (net (code "40") (name "Net-(IC2F-VDD_AFE)") (class "Default")
      (node (ref "C170") (pin "1") (pinfunction "1_1") (pintype "passive"))
      (node (ref "FR59") (pin "1") (pinfunction "1_1") (pintype "passive"))
      (node (ref "IC2") (pin "AJ25") (pinfunction "VDD_AFE_AJ25") (pintype "power_in"))
    )
    (net (code "41") (name "Net-(IC2F-VDD_CP_CGEN)") (class "Default")
      (node (ref "C158") (pin "1") (pinfunction "1_1") (pintype "passive"))
      (node (ref "IC2") (pin "F20") (pinfunction "VDD_CP_CGEN_F20") (pintype "power_in"))
      (node (ref "R70") (pin "2") (pinfunction "2_2") (pintype "passive"))
    )
    (net (code "42") (name "Net-(IC2F-VDD_CP_SXR)") (class "Default")
      (node (ref "C163") (pin "1") (pinfunction "1_1") (pintype "passive"))
      (node (ref "IC2") (pin "AL19") (pinfunction "VDD_CP_SXR_AL19") (pintype "power_in"))
      (node (ref "R68") (pin "2") (pinfunction "2_2") (pintype "passive"))
    )
    (net (code "43") (name "Net-(IC2F-VDD_CP_SXT)") (class "Default")
      (node (ref "C166") (pin "1") (pinfunction "1_1") (pintype "passive"))
      (node (ref "IC2") (pin "J3") (pinfunction "VDD_CP_SXT_J3") (pintype "power_in"))
      (node (ref "R67") (pin "1") (pinfunction "1_1") (pintype "passive"))
    )
    (net (code "44") (name "Net-(IC2F-VDD_DIV_CGEN)") (class "Default")
      (node (ref "C157") (pin "1") (pinfunction "1_1") (pintype "passive"))
      (node (ref "FR61") (pin "1") (pinfunction "1_1") (pintype "passive"))
      (node (ref "IC2") (pin "E19") (pinfunction "VDD_DIV_CGEN_E19") (pintype "power_in"))
    )
    (net (code "45") (name "Net-(IC2F-VDD_DIV_SXR)") (class "Default")
      (node (ref "C162") (pin "1") (pinfunction "1_1") (pintype "passive"))
      (node (ref "FR56") (pin "1") (pinfunction "1_1") (pintype "passive"))
      (node (ref "IC2") (pin "AM20") (pinfunction "VDD_DIV_SXR_AM20") (pintype "power_in"))
    )
    (net (code "46") (name "Net-(IC2F-VDD_DIV_SXT)") (class "Default")
      (node (ref "C175") (pin "1") (pinfunction "1_1") (pintype "passive"))
      (node (ref "FR63") (pin "2") (pinfunction "2_2") (pintype "passive"))
      (node (ref "FR64") (pin "2") (pinfunction "2_2") (pintype "passive"))
      (node (ref "IC2") (pin "L5") (pinfunction "VDD_DIV_SXT_L5") (pintype "power_in"))
      (node (ref "R72") (pin "2") (pinfunction "2_2") (pintype "passive"))
    )
    (net (code "47") (name "Net-(IC2F-VDD_MXLOBUF_RFE)") (class "Default")
      (node (ref "C171") (pin "1") (pinfunction "1_1") (pintype "passive"))
      (node (ref "FR65") (pin "1") (pinfunction "1_1") (pintype "passive"))
      (node (ref "FR66") (pin "1") (pinfunction "1_1") (pintype "passive"))
      (node (ref "IC2") (pin "AN17") (pinfunction "VDD_MXLOBUF_RFE_AN17") (pintype "power_in"))
    )
    (net (code "48") (name "Net-(IC2F-VDD_SPI_BUF)") (class "Default")
      (node (ref "C150") (pin "1") (pinfunction "1_1") (pintype "passive"))
      (node (ref "FR49") (pin "2") (pinfunction "2_2") (pintype "passive"))
      (node (ref "IC2") (pin "F24") (pinfunction "VDD_SPI_BUF_F24") (pintype "power_in"))
    )
    (net (code "49") (name "Net-(IC2F-VDD_TBB)") (class "Default")
      (node (ref "C154") (pin "1") (pinfunction "1_1") (pintype "passive"))
      (node (ref "FR53") (pin "2") (pinfunction "2_2") (pintype "passive"))
      (node (ref "IC2") (pin "P4") (pinfunction "VDD_TBB_P4") (pintype "power_in"))
    )
    (net (code "50") (name "Net-(IC2F-VDD_TLOBUF_TRF)") (class "Default")
      (node (ref "C156") (pin "1") (pinfunction "1_1") (pintype "passive"))
      (node (ref "FR62") (pin "1") (pinfunction "1_1") (pintype "passive"))
      (node (ref "IC2") (pin "F8") (pinfunction "VDD_TLOBUF_TRF_F8") (pintype "power_in"))
      (node (ref "R71") (pin "1") (pinfunction "1_1") (pintype "passive"))
    )
    (net (code "51") (name "Net-(IC2F-VDD_TPAD_TRF)") (class "Default")
      (node (ref "C155") (pin "1") (pinfunction "1_1") (pintype "passive"))
      (node (ref "FR60") (pin "1") (pinfunction "1_1") (pintype "passive"))
      (node (ref "IC2") (pin "B16") (pinfunction "VDD_TPAD_TRF_B16") (pintype "power_in"))
    )
    (net (code "52") (name "VCC1P4_LMS2") (class "Default")
      (node (ref "FR64") (pin "1") (pinfunction "1_1") (pintype "passive"))
      (node (ref "FR65") (pin "2") (pinfunction "2_2") (pintype "passive"))
      (node (ref "FR67") (pin "2") (pinfunction "2_2") (pintype "passive"))
      (node (ref "FR68") (pin "2") (pinfunction "2_2") (pintype "passive"))
      (node (ref "FR69") (pin "2") (pinfunction "2_2") (pintype "passive"))
      (node (ref "FR70") (pin "2") (pinfunction "2_2") (pintype "passive"))
    )
    (net (code "53") (name "VCC1P8_LMS2_B") (class "Default")
      (node (ref "FR36") (pin "2") (pinfunction "2_2") (pintype "passive"))
      (node (ref "FR37") (pin "1") (pinfunction "1_1") (pintype "passive"))
      (node (ref "FR38") (pin "1") (pinfunction "1_1") (pintype "passive"))
      (node (ref "FR39") (pin "2") (pinfunction "2_2") (pintype "passive"))
      (node (ref "FR40") (pin "2") (pinfunction "2_2") (pintype "passive"))
      (node (ref "FR41") (pin "2") (pinfunction "2_2") (pintype "passive"))
      (node (ref "FR42") (pin "2") (pinfunction "2_2") (pintype "passive"))
      (node (ref "FR43") (pin "2") (pinfunction "2_2") (pintype "passive"))
      (node (ref "R56") (pin "2") (pinfunction "2_2") (pintype "passive"))
      (node (ref "R59") (pin "2") (pinfunction "2_2") (pintype "passive"))
      (node (ref "R60") (pin "1") (pinfunction "1_1") (pintype "passive"))
    )
    (net (code "54") (name "VCC1P25_LMS2") (class "Default")
      (node (ref "FR46") (pin "1") (pinfunction "1_1") (pintype "passive"))
      (node (ref "FR47") (pin "1") (pinfunction "1_1") (pintype "passive"))
      (node (ref "FR48") (pin "1") (pinfunction "1_1") (pintype "passive"))
      (node (ref "FR49") (pin "1") (pinfunction "1_1") (pintype "passive"))
      (node (ref "FR50") (pin "2") (pinfunction "2_2") (pintype "passive"))
      (node (ref "FR52") (pin "1") (pinfunction "1_1") (pintype "passive"))
      (node (ref "FR53") (pin "1") (pinfunction "1_1") (pintype "passive"))
      (node (ref "FR54") (pin "1") (pinfunction "1_1") (pintype "passive"))
      (node (ref "FR55") (pin "1") (pinfunction "1_1") (pintype "passive"))
      (node (ref "FR56") (pin "2") (pinfunction "2_2") (pintype "passive"))
      (node (ref "FR57") (pin "2") (pinfunction "2_2") (pintype "passive"))
      (node (ref "FR59") (pin "2") (pinfunction "2_2") (pintype "passive"))
      (node (ref "FR60") (pin "2") (pinfunction "2_2") (pintype "passive"))
      (node (ref "FR61") (pin "2") (pinfunction "2_2") (pintype "passive"))
      (node (ref "FR62") (pin "2") (pinfunction "2_2") (pintype "passive"))
      (node (ref "FR63") (pin "1") (pinfunction "1_1") (pintype "passive"))
      (node (ref "FR66") (pin "2") (pinfunction "2_2") (pintype "passive"))
      (node (ref "R65") (pin "2") (pinfunction "2_2") (pintype "passive"))
      (node (ref "R67") (pin "2") (pinfunction "2_2") (pintype "passive"))
      (node (ref "R68") (pin "1") (pinfunction "1_1") (pintype "passive"))
      (node (ref "R69") (pin "1") (pinfunction "1_1") (pintype "passive"))
      (node (ref "R70") (pin "1") (pinfunction "1_1") (pintype "passive"))
    )
    (net (code "55") (name "VCC1P25_LMS2_DIG") (class "Default")
      (node (ref "R63") (pin "2") (pinfunction "2_2") (pintype "passive"))
      (node (ref "R64") (pin "2") (pinfunction "2_2") (pintype "passive"))
    )
    (net (code "56") (name "VDIO_LMS2") (class "Default")
      (node (ref "C139") (pin "2") (pinfunction "2_2") (pintype "passive"))
      (node (ref "C140") (pin "2") (pinfunction "2_2") (pintype "passive"))
      (node (ref "IC5") (pin "8") (pinfunction "VCC_8") (pintype "passive"))
      (node (ref "IC6") (pin "1") (pinfunction "A0_1") (pintype "passive"))
      (node (ref "IC6") (pin "2") (pinfunction "A1_2") (pintype "passive"))
      (node (ref "IC6") (pin "3") (pinfunction "A2_3") (pintype "passive"))
      (node (ref "IC6") (pin "8") (pinfunction "VCC_8") (pintype "passive"))
      (node (ref "R57") (pin "1") (pinfunction "1_1") (pintype "passive"))
      (node (ref "R58") (pin "1") (pinfunction "1_1") (pintype "passive"))
      (node (ref "R61") (pin "1") (pinfunction "1_1") (pintype "passive"))
      (node (ref "R62") (pin "1") (pinfunction "1_1") (pintype "passive"))
    )
  )
)
